# FemaleHeader.net
KiCad netlist of a schematic drawn in Altium Designer
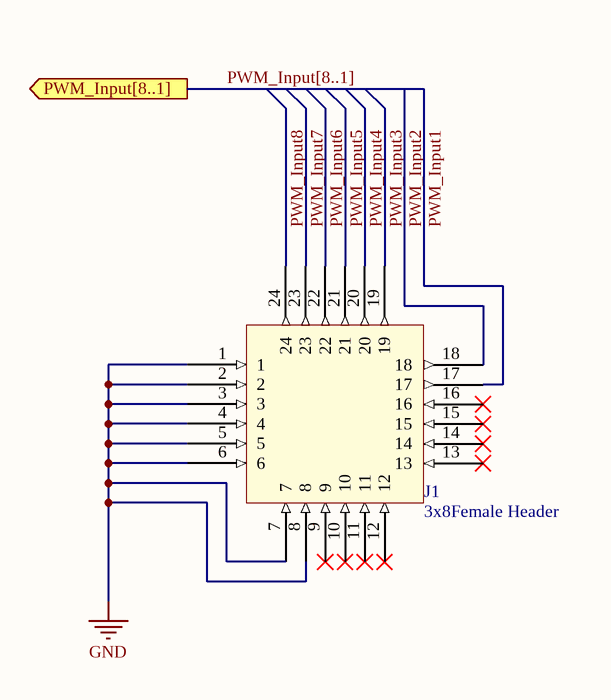
[diagram p0: FemaleHeader.SchDoc]

(export (version "E")
  (design (tool "Eeschema 10.0.6"))
  (components
    (comp (ref "J1")
      (value "3x8Female Header")
      (footprint "3x8 Female Header")
      (description "3x8 female header")
      (fields (field (name "MANUFACTURER") "URC") (field (name "MANUFACTURER PART NUMBER") "Custom"))
      (libsource (lib "3x8 Female Header") (part "3x8 Female Header"))
    )
  )
  (nets
    (net (code "1") (name "/PWM_Input1") (class "Default")
      (node (ref "J1") (pin "17") (pinfunction "17_17") (pintype "output"))
    )
    (net (code "2") (name "/PWM_Input2") (class "Default")
      (node (ref "J1") (pin "18") (pinfunction "18_18") (pintype "output"))
    )
    (net (code "3") (name "/PWM_Input3") (class "Default")
      (node (ref "J1") (pin "19") (pinfunction "19_19") (pintype "output"))
    )
    (net (code "4") (name "/PWM_Input4") (class "Default")
      (node (ref "J1") (pin "20") (pinfunction "20_20") (pintype "output"))
    )
    (net (code "5") (name "/PWM_Input5") (class "Default")
      (node (ref "J1") (pin "21") (pinfunction "21_21") (pintype "output"))
    )
    (net (code "6") (name "/PWM_Input6") (class "Default")
      (node (ref "J1") (pin "22") (pinfunction "22_22") (pintype "output"))
    )
    (net (code "7") (name "/PWM_Input7") (class "Default")
      (node (ref "J1") (pin "23") (pinfunction "23_23") (pintype "output"))
    )
    (net (code "8") (name "/PWM_Input8") (class "Default")
      (node (ref "J1") (pin "24") (pinfunction "24_24") (pintype "output"))
    )
    (net (code "10") (name "GND") (class "Default")
      (node (ref "J1") (pin "1") (pinfunction "1_1") (pintype "input"))
      (node (ref "J1") (pin "2") (pinfunction "2_2") (pintype "input"))
      (node (ref "J1") (pin "3") (pinfunction "3_3") (pintype "input"))
      (node (ref "J1") (pin "4") (pinfunction "4_4") (pintype "input"))
      (node (ref "J1") (pin "5") (pinfunction "5_5") (pintype "input"))
      (node (ref "J1") (pin "6") (pinfunction "6_6") (pintype "input"))
      (node (ref "J1") (pin "7") (pinfunction "7_7") (pintype "input"))
      (node (ref "J1") (pin "8") (pinfunction "8_8") (pintype "input"))
    )
    (net (code "11") (name "unconnected-(J1-Pad9)") (class "Default")
      (node (ref "J1") (pin "9") (pinfunction "9_9") (pintype "input+no_connect"))
    )
    (net (code "12") (name "unconnected-(J1-Pad10)") (class "Default")
      (node (ref "J1") (pin "10") (pinfunction "10_10") (pintype "input+no_connect"))
    )
    (net (code "13") (name "unconnected-(J1-Pad11)") (class "Default")
      (node (ref "J1") (pin "11") (pinfunction "11_11") (pintype "input+no_connect"))
    )
    (net (code "14") (name "unconnected-(J1-Pad12)") (class "Default")
      (node (ref "J1") (pin "12") (pinfunction "12_12") (pintype "input+no_connect"))
    )
    (net (code "15") (name "unconnected-(J1-Pad13)") (class "Default")
      (node (ref "J1") (pin "13") (pinfunction "13_13") (pintype "input+no_connect"))
    )
    (net (code "16") (name "unconnected-(J1-Pad14)") (class "Default")
      (node (ref "J1") (pin "14") (pinfunction "14_14") (pintype "input+no_connect"))
    )
    (net (code "17") (name "unconnected-(J1-Pad15)") (class "Default")
      (node (ref "J1") (pin "15") (pinfunction "15_15") (pintype "input+no_connect"))
    )
    (net (code "18") (name "unconnected-(J1-Pad16)") (class "Default")
      (node (ref "J1") (pin "16") (pinfunction "16_16") (pintype "input+no_connect"))
    )
  )
)
